# SmartShell_Schematic.net
KiCad netlist of a schematic drawn in Altium Designer
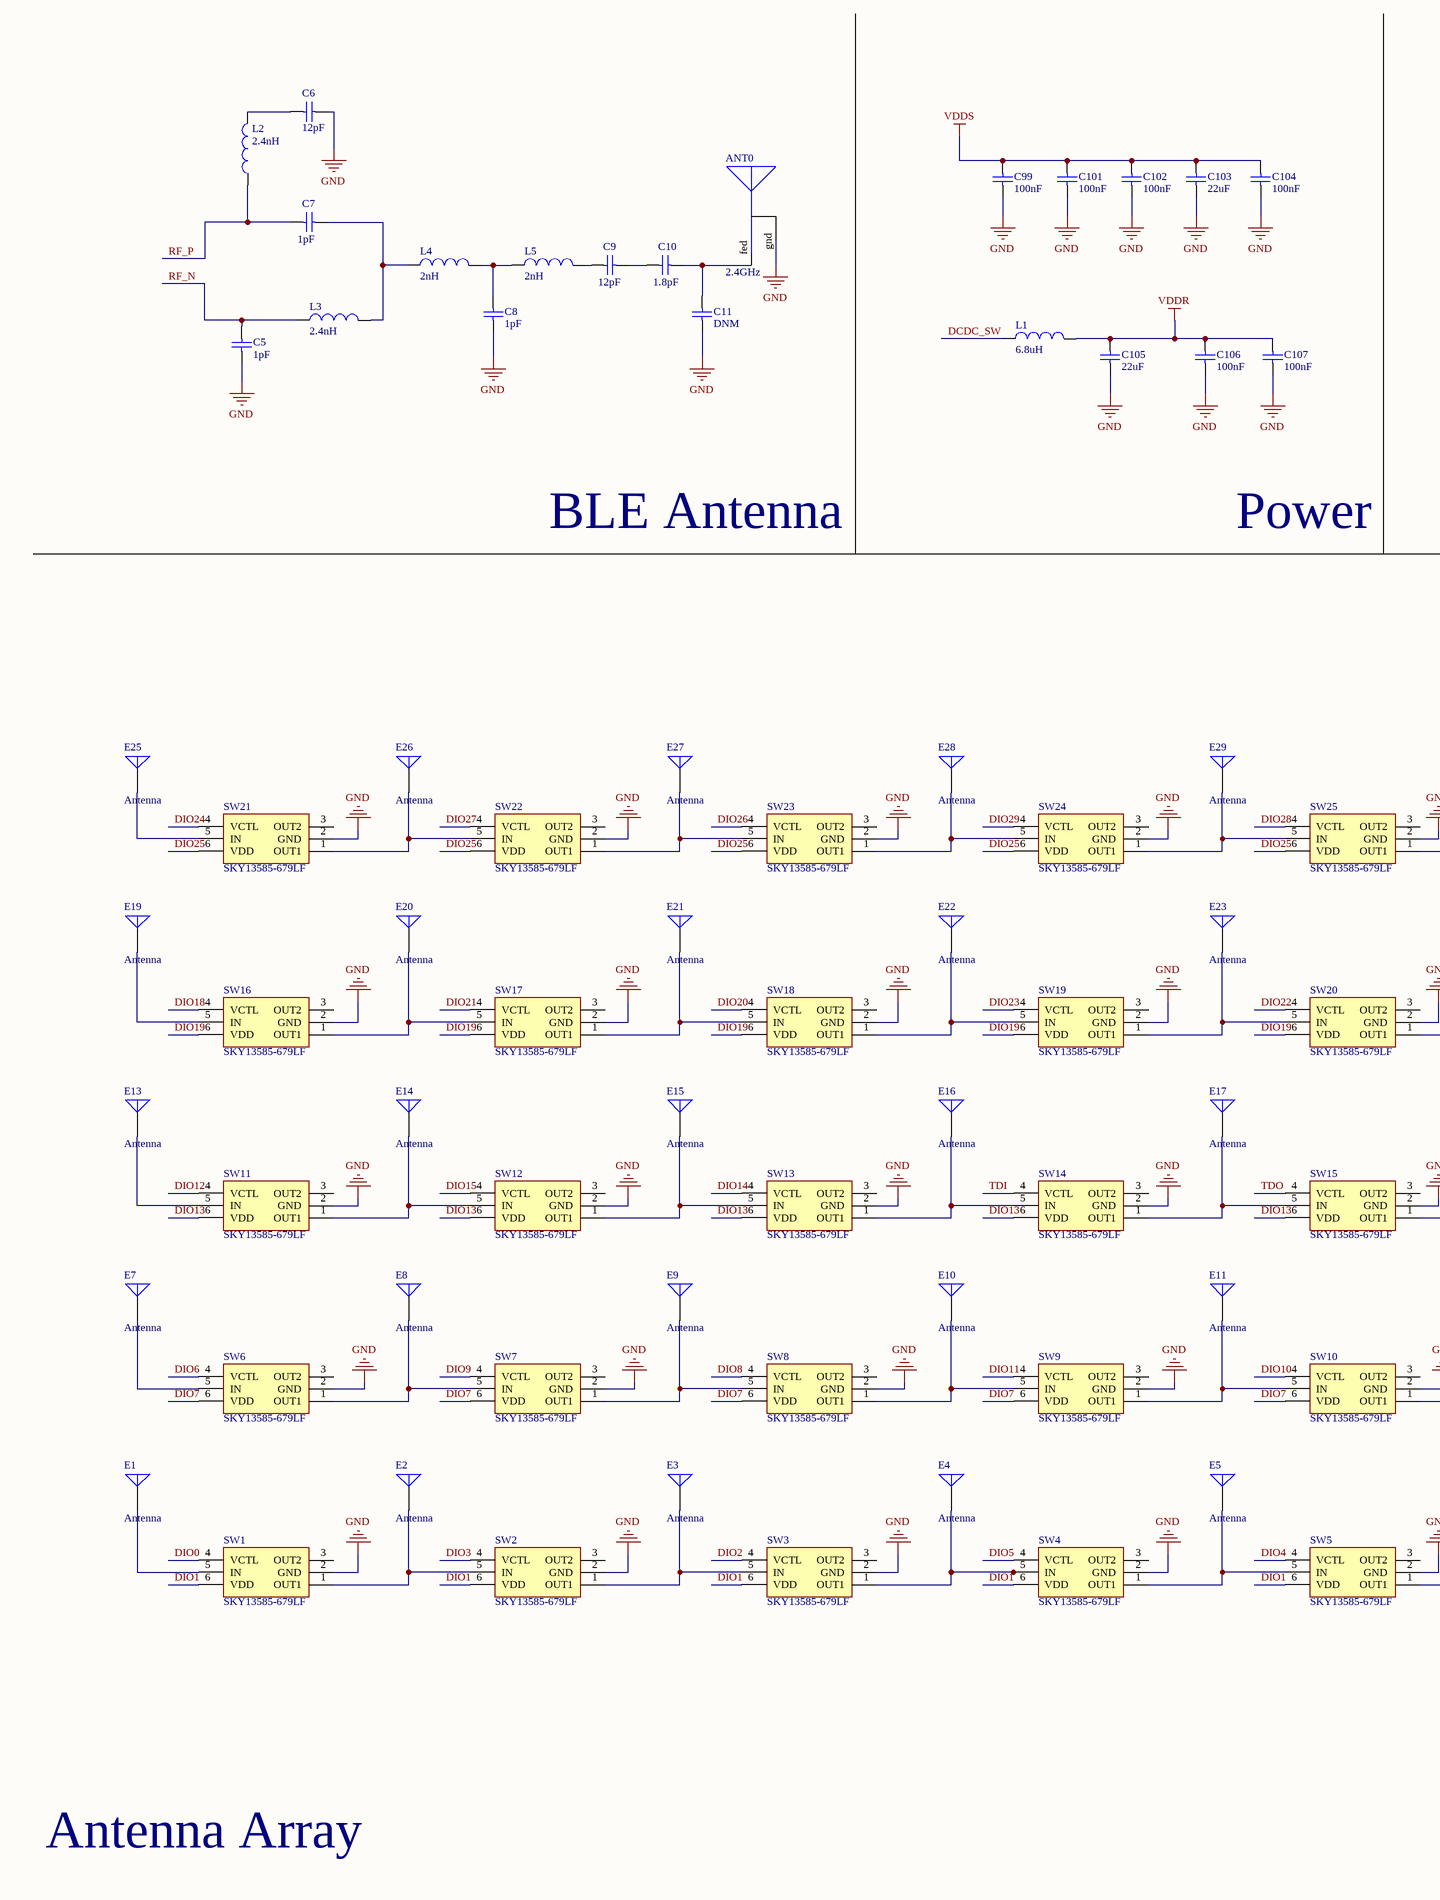
[diagram p0: SmartShell_Schematic.SchDoc, left]
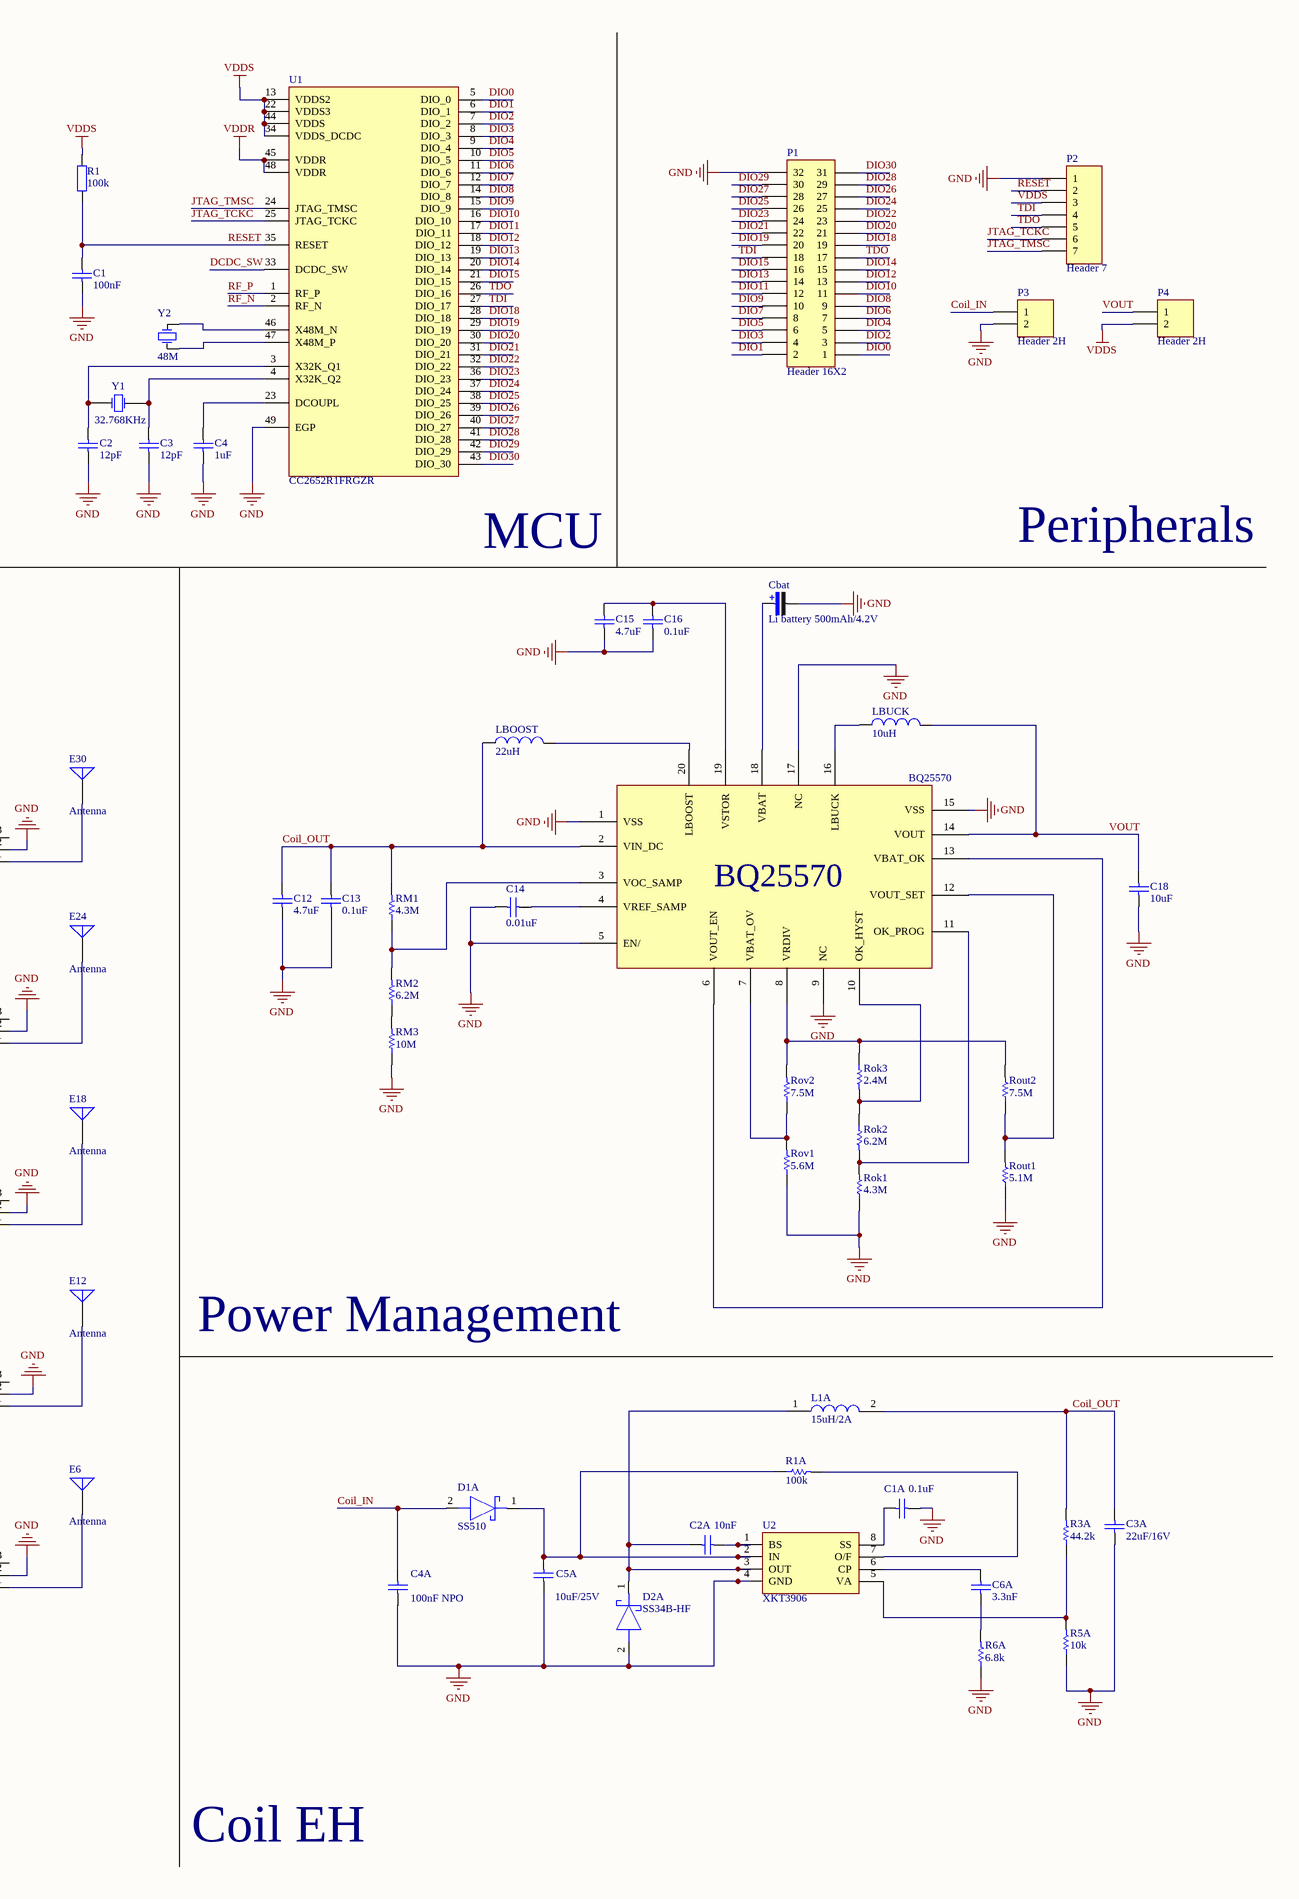
[diagram p1: SmartShell_Schematic.SchDoc, right]

(export (version "E")
  (design (tool "Eeschema 10.0.6"))
  (components
    (comp (ref "ANT0")
      (value "2.4GHz")
      (footprint "PCBComponent_1")
      (description "2.4GHz small RF-antenna")
      (libsource (lib "ant043") (part "AN043"))
    )
    (comp (ref "BQ25570") (value "~") (libsource (lib "bq25570") (part "Component_1")))
    (comp (ref "C1")
      (value "100nF")
      (footprint "C-0603")
      (description "贴片瓷片电容")
      (fields (field (name "Comment") "Cap-S") (field (name "PUBLISHER") "Altium Limited"))
      (libsource (lib "fszhang") (part "Cap-S"))
    )
    (comp (ref "C1A")
      (value "0.1uF")
      (footprint "0603")
      (description "Capacitor")
      (fields (field (name "Comment") "Cap") (field (name "PUBLISHER") "Altium Limited"))
      (libsource (lib "Miscellaneous Devices") (part "Cap"))
    )
    (comp (ref "C2")
      (value "12pF")
      (footprint "C-0603")
      (description "贴片瓷片电容")
      (fields (field (name "Comment") "Cap-S") (field (name "PUBLISHER") "Altium Limited"))
      (libsource (lib "fszhang") (part "Cap-S"))
    )
    (comp (ref "C2A")
      (value "10nF")
      (footprint "0603")
      (description "Capacitor")
      (fields (field (name "Comment") "Cap") (field (name "PUBLISHER") "Altium Limited"))
      (libsource (lib "Miscellaneous Devices") (part "Cap"))
    )
    (comp (ref "C3")
      (value "12pF")
      (footprint "C-0603")
      (description "贴片瓷片电容")
      (fields (field (name "Comment") "Cap-S") (field (name "PUBLISHER") "Altium Limited"))
      (libsource (lib "fszhang") (part "Cap-S"))
    )
    (comp (ref "C3A")
      (value "22uF/16V")
      (footprint "1206")
      (description "Capacitor")
      (fields (field (name "Comment") "Cap") (field (name "PUBLISHER") "Altium Limited"))
      (libsource (lib "Miscellaneous Devices") (part "Cap"))
    )
    (comp (ref "C4")
      (value "1uF")
      (footprint "C-0603")
      (description "贴片瓷片电容")
      (fields (field (name "Comment") "Cap-S") (field (name "PUBLISHER") "Altium Limited"))
      (libsource (lib "fszhang") (part "Cap-S"))
    )
    (comp (ref "C4A")
      (value "100nF NPO")
      (footprint "1206")
      (description "Capacitor")
      (fields (field (name "Comment") "Cap") (field (name "PUBLISHER") "Altium Limited"))
      (libsource (lib "Miscellaneous Devices") (part "Cap"))
    )
    (comp (ref "C5")
      (value "1pF")
      (footprint "RAD-0.3")
      (description "Capacitor")
      (fields (field (name "PUBLISHER") "Altium Limited"))
      (libsource (lib "Miscellaneous Devices") (part "Cap"))
    )
    (comp (ref "C5A")
      (value "10uF/25V")
      (footprint "1206")
      (description "Capacitor")
      (fields (field (name "Comment") "Cap") (field (name "PUBLISHER") "Altium Limited"))
      (libsource (lib "Miscellaneous Devices") (part "Cap"))
    )
    (comp (ref "C6")
      (value "12pF")
      (footprint "RAD-0.3")
      (description "Capacitor")
      (fields (field (name "PUBLISHER") "Altium Limited"))
      (libsource (lib "Miscellaneous Devices") (part "Cap"))
    )
    (comp (ref "C6A")
      (value "3.3nF")
      (footprint "0603")
      (description "Capacitor")
      (fields (field (name "Comment") "Cap") (field (name "PUBLISHER") "Altium Limited"))
      (libsource (lib "Miscellaneous Devices") (part "Cap"))
    )
    (comp (ref "C7")
      (value "1pF")
      (footprint "RAD-0.3")
      (description "Capacitor")
      (fields (field (name "PUBLISHER") "Altium Limited"))
      (libsource (lib "Miscellaneous Devices") (part "Cap"))
    )
    (comp (ref "C8")
      (value "1pF")
      (footprint "RAD-0.3")
      (description "Capacitor")
      (fields (field (name "PUBLISHER") "Altium Limited"))
      (libsource (lib "Miscellaneous Devices") (part "Cap"))
    )
    (comp (ref "C9")
      (value "12pF")
      (footprint "RAD-0.3")
      (description "Capacitor")
      (fields (field (name "PUBLISHER") "Altium Limited"))
      (libsource (lib "Miscellaneous Devices") (part "Cap"))
    )
    (comp (ref "C10")
      (value "1.8pF")
      (footprint "RAD-0.3")
      (description "Capacitor")
      (fields (field (name "PUBLISHER") "Altium Limited"))
      (libsource (lib "Miscellaneous Devices") (part "Cap"))
    )
    (comp (ref "C11")
      (value "DNM")
      (footprint "RAD-0.3")
      (description "Capacitor")
      (fields (field (name "PUBLISHER") "Altium Limited"))
      (libsource (lib "Miscellaneous Devices") (part "Cap"))
    )
    (comp (ref "C12")
      (value "4.7uF")
      (footprint "1608[0603]")
      (description "Capacitor")
      (fields (field (name "PUBLISHER") "Altium Limited"))
      (libsource (lib "Miscellaneous Devices") (part "Cap"))
    )
    (comp (ref "C13")
      (value "0.1uF")
      (footprint "1608[0603]")
      (description "Capacitor")
      (fields (field (name "PUBLISHER") "Altium Limited"))
      (libsource (lib "Miscellaneous Devices") (part "Cap"))
    )
    (comp (ref "C14")
      (value "0.01uF")
      (footprint "1608[0603]")
      (description "Capacitor")
      (fields (field (name "PUBLISHER") "Altium Limited"))
      (libsource (lib "Miscellaneous Devices") (part "Cap"))
    )
    (comp (ref "C15")
      (value "4.7uF")
      (footprint "1608[0603]")
      (description "Capacitor")
      (fields (field (name "PUBLISHER") "Altium Limited"))
      (libsource (lib "Miscellaneous Devices") (part "Cap"))
    )
    (comp (ref "C16")
      (value "0.1uF")
      (footprint "1608[0603]")
      (description "Capacitor")
      (fields (field (name "PUBLISHER") "Altium Limited"))
      (libsource (lib "Miscellaneous Devices") (part "Cap"))
    )
    (comp (ref "C18")
      (value "10uF")
      (footprint "1608[0603]")
      (description "Capacitor")
      (fields (field (name "PUBLISHER") "Altium Limited"))
      (libsource (lib "Miscellaneous Devices") (part "Cap"))
    )
    (comp (ref "C99")
      (value "100nF")
      (footprint "C-0603")
      (description "贴片瓷片电容")
      (fields (field (name "Comment") "Cap-S") (field (name "PUBLISHER") "Altium Limited"))
      (libsource (lib "fszhang") (part "Cap-S"))
    )
    (comp (ref "C101")
      (value "100nF")
      (footprint "C-0603")
      (description "贴片瓷片电容")
      (fields (field (name "Comment") "Cap-S") (field (name "PUBLISHER") "Altium Limited"))
      (libsource (lib "fszhang") (part "Cap-S"))
    )
    (comp (ref "C102")
      (value "100nF")
      (footprint "C-0603")
      (description "贴片瓷片电容")
      (fields (field (name "Comment") "Cap-S") (field (name "PUBLISHER") "Altium Limited"))
      (libsource (lib "fszhang") (part "Cap-S"))
    )
    (comp (ref "C103")
      (value "22uF")
      (footprint "C-0603")
      (description "贴片瓷片电容")
      (fields (field (name "Comment") "Cap-S") (field (name "PUBLISHER") "Altium Limited"))
      (libsource (lib "fszhang") (part "Cap-S"))
    )
    (comp (ref "C104")
      (value "100nF")
      (footprint "C-0603")
      (description "贴片瓷片电容")
      (fields (field (name "Comment") "Cap-S") (field (name "PUBLISHER") "Altium Limited"))
      (libsource (lib "fszhang") (part "Cap-S"))
    )
    (comp (ref "C105")
      (value "22uF")
      (footprint "C-0603")
      (description "贴片瓷片电容")
      (fields (field (name "Comment") "Cap-S") (field (name "PUBLISHER") "Altium Limited"))
      (libsource (lib "fszhang") (part "Cap-S"))
    )
    (comp (ref "C106")
      (value "100nF")
      (footprint "C-0603")
      (description "贴片瓷片电容")
      (fields (field (name "Comment") "Cap-S") (field (name "PUBLISHER") "Altium Limited"))
      (libsource (lib "fszhang") (part "Cap-S"))
    )
    (comp (ref "C107")
      (value "100nF")
      (footprint "C-0603")
      (description "贴片瓷片电容")
      (fields (field (name "Comment") "Cap-S") (field (name "PUBLISHER") "Altium Limited"))
      (libsource (lib "fszhang") (part "Cap-S"))
    )
    (comp (ref "Cbat")
      (value "Li battery 500mAh/4.2V")
      (footprint "C-RB-SD6")
      (description "贴片铝电解电容")
      (fields (field (name "Comment") "Cap-Pol-ES") (field (name "PUBLISHER") "Altium Limited"))
      (libsource (lib "fszhang") (part "Cap-Pol-ES"))
    )
    (comp (ref "D1A")
      (value "SS510")
      (footprint "SamacSys:DIOM7959X262N")
      (description "Schottky Diode")
      (libsource (lib "SamacSys") (part "SS510"))
    )
    (comp (ref "D2A")
      (value "SS34B-HF")
      (footprint "SamacSys:DIOM5336X320N")
      (description "Schottky Diode")
      (libsource (lib "SamacSys") (part "SS34B-HF"))
    )
    (comp (ref "E1")
      (value "Antenna")
      (footprint "PIN1")
      (description "Generic Antenna")
      (fields (field (name "PUBLISHER") "Altium Limited"))
      (libsource (lib "Miscellaneous Devices") (part "Antenna"))
    )
    (comp (ref "E2")
      (value "Antenna")
      (footprint "PIN1")
      (description "Generic Antenna")
      (fields (field (name "PUBLISHER") "Altium Limited"))
      (libsource (lib "Miscellaneous Devices") (part "Antenna"))
    )
    (comp (ref "E3")
      (value "Antenna")
      (footprint "PIN1")
      (description "Generic Antenna")
      (fields (field (name "PUBLISHER") "Altium Limited"))
      (libsource (lib "Miscellaneous Devices") (part "Antenna"))
    )
    (comp (ref "E4")
      (value "Antenna")
      (footprint "PIN1")
      (description "Generic Antenna")
      (fields (field (name "PUBLISHER") "Altium Limited"))
      (libsource (lib "Miscellaneous Devices") (part "Antenna"))
    )
    (comp (ref "E5")
      (value "Antenna")
      (footprint "PIN1")
      (description "Generic Antenna")
      (fields (field (name "PUBLISHER") "Altium Limited"))
      (libsource (lib "Miscellaneous Devices") (part "Antenna"))
    )
    (comp (ref "E6")
      (value "Antenna")
      (footprint "PIN1")
      (description "Generic Antenna")
      (fields (field (name "PUBLISHER") "Altium Limited"))
      (libsource (lib "Miscellaneous Devices") (part "Antenna"))
    )
    (comp (ref "E7")
      (value "Antenna")
      (footprint "PIN1")
      (description "Generic Antenna")
      (fields (field (name "PUBLISHER") "Altium Limited"))
      (libsource (lib "Miscellaneous Devices") (part "Antenna"))
    )
    (comp (ref "E8")
      (value "Antenna")
      (footprint "PIN1")
      (description "Generic Antenna")
      (fields (field (name "PUBLISHER") "Altium Limited"))
      (libsource (lib "Miscellaneous Devices") (part "Antenna"))
    )
    (comp (ref "E9")
      (value "Antenna")
      (footprint "PIN1")
      (description "Generic Antenna")
      (fields (field (name "PUBLISHER") "Altium Limited"))
      (libsource (lib "Miscellaneous Devices") (part "Antenna"))
    )
    (comp (ref "E10")
      (value "Antenna")
      (footprint "PIN1")
      (description "Generic Antenna")
      (fields (field (name "PUBLISHER") "Altium Limited"))
      (libsource (lib "Miscellaneous Devices") (part "Antenna"))
    )
    (comp (ref "E11")
      (value "Antenna")
      (footprint "PIN1")
      (description "Generic Antenna")
      (fields (field (name "PUBLISHER") "Altium Limited"))
      (libsource (lib "Miscellaneous Devices") (part "Antenna"))
    )
    (comp (ref "E12")
      (value "Antenna")
      (footprint "PIN1")
      (description "Generic Antenna")
      (fields (field (name "PUBLISHER") "Altium Limited"))
      (libsource (lib "Miscellaneous Devices") (part "Antenna"))
    )
    (comp (ref "E13")
      (value "Antenna")
      (footprint "PIN1")
      (description "Generic Antenna")
      (fields (field (name "PUBLISHER") "Altium Limited"))
      (libsource (lib "Miscellaneous Devices") (part "Antenna"))
    )
    (comp (ref "E14")
      (value "Antenna")
      (footprint "PIN1")
      (description "Generic Antenna")
      (fields (field (name "PUBLISHER") "Altium Limited"))
      (libsource (lib "Miscellaneous Devices") (part "Antenna"))
    )
    (comp (ref "E15")
      (value "Antenna")
      (footprint "PIN1")
      (description "Generic Antenna")
      (fields (field (name "PUBLISHER") "Altium Limited"))
      (libsource (lib "Miscellaneous Devices") (part "Antenna"))
    )
    (comp (ref "E16")
      (value "Antenna")
      (footprint "PIN1")
      (description "Generic Antenna")
      (fields (field (name "PUBLISHER") "Altium Limited"))
      (libsource (lib "Miscellaneous Devices") (part "Antenna"))
    )
    (comp (ref "E17")
      (value "Antenna")
      (footprint "PIN1")
      (description "Generic Antenna")
      (fields (field (name "PUBLISHER") "Altium Limited"))
      (libsource (lib "Miscellaneous Devices") (part "Antenna"))
    )
    (comp (ref "E18")
      (value "Antenna")
      (footprint "PIN1")
      (description "Generic Antenna")
      (fields (field (name "PUBLISHER") "Altium Limited"))
      (libsource (lib "Miscellaneous Devices") (part "Antenna"))
    )
    (comp (ref "E19")
      (value "Antenna")
      (footprint "PIN1")
      (description "Generic Antenna")
      (fields (field (name "PUBLISHER") "Altium Limited"))
      (libsource (lib "Miscellaneous Devices") (part "Antenna"))
    )
    (comp (ref "E20")
      (value "Antenna")
      (footprint "PIN1")
      (description "Generic Antenna")
      (fields (field (name "PUBLISHER") "Altium Limited"))
      (libsource (lib "Miscellaneous Devices") (part "Antenna"))
    )
    (comp (ref "E21")
      (value "Antenna")
      (footprint "PIN1")
      (description "Generic Antenna")
      (fields (field (name "PUBLISHER") "Altium Limited"))
      (libsource (lib "Miscellaneous Devices") (part "Antenna"))
    )
    (comp (ref "E22")
      (value "Antenna")
      (footprint "PIN1")
      (description "Generic Antenna")
      (fields (field (name "PUBLISHER") "Altium Limited"))
      (libsource (lib "Miscellaneous Devices") (part "Antenna"))
    )
    (comp (ref "E23")
      (value "Antenna")
      (footprint "PIN1")
      (description "Generic Antenna")
      (fields (field (name "PUBLISHER") "Altium Limited"))
      (libsource (lib "Miscellaneous Devices") (part "Antenna"))
    )
    (comp (ref "E24")
      (value "Antenna")
      (footprint "PIN1")
      (description "Generic Antenna")
      (fields (field (name "PUBLISHER") "Altium Limited"))
      (libsource (lib "Miscellaneous Devices") (part "Antenna"))
    )
    (comp (ref "E25")
      (value "Antenna")
      (footprint "PIN1")
      (description "Generic Antenna")
      (fields (field (name "PUBLISHER") "Altium Limited"))
      (libsource (lib "Miscellaneous Devices") (part "Antenna"))
    )
    (comp (ref "E26")
      (value "Antenna")
      (footprint "PIN1")
      (description "Generic Antenna")
      (fields (field (name "PUBLISHER") "Altium Limited"))
      (libsource (lib "Miscellaneous Devices") (part "Antenna"))
    )
    (comp (ref "E27")
      (value "Antenna")
      (footprint "PIN1")
      (description "Generic Antenna")
      (fields (field (name "PUBLISHER") "Altium Limited"))
      (libsource (lib "Miscellaneous Devices") (part "Antenna"))
    )
    (comp (ref "E28")
      (value "Antenna")
      (footprint "PIN1")
      (description "Generic Antenna")
      (fields (field (name "PUBLISHER") "Altium Limited"))
      (libsource (lib "Miscellaneous Devices") (part "Antenna"))
    )
    (comp (ref "E29")
      (value "Antenna")
      (footprint "PIN1")
      (description "Generic Antenna")
      (fields (field (name "PUBLISHER") "Altium Limited"))
      (libsource (lib "Miscellaneous Devices") (part "Antenna"))
    )
    (comp (ref "E30")
      (value "Antenna")
      (footprint "PIN1")
      (description "Generic Antenna")
      (fields (field (name "PUBLISHER") "Altium Limited"))
      (libsource (lib "Miscellaneous Devices") (part "Antenna"))
    )
    (comp (ref "L1")
      (value "6.8uH")
      (footprint "0402-A")
      (description "Inductor")
      (fields (field (name "PUBLISHER") "Altium Limited"))
      (libsource (lib "Miscellaneous Devices") (part "Inductor"))
    )
    (comp (ref "L1A")
      (value "15uH/2A")
      (footprint "SamacSys:CD73NP331KC")
      (description "Inductor")
      (fields
        (field (name "MANUFACTURER_PART_NUMBER") "CD73NP-331KC")
        (field (name "MOUSER PART NUMBER") "851-CD73NP-331KC")
      )
      (libsource (lib "SamacSys") (part "CD73NP-331KC"))
    )
    (comp (ref "L2")
      (value "2.4nH")
      (footprint "0402-A")
      (description "Inductor")
      (fields (field (name "PUBLISHER") "Altium Limited"))
      (libsource (lib "Miscellaneous Devices") (part "Inductor"))
    )
    (comp (ref "L3")
      (value "2.4nH")
      (footprint "0402-A")
      (description "Inductor")
      (fields (field (name "PUBLISHER") "Altium Limited"))
      (libsource (lib "Miscellaneous Devices") (part "Inductor"))
    )
    (comp (ref "L4")
      (value "2nH")
      (footprint "0402-A")
      (description "Inductor")
      (fields (field (name "PUBLISHER") "Altium Limited"))
      (libsource (lib "Miscellaneous Devices") (part "Inductor"))
    )
    (comp (ref "L5")
      (value "2nH")
      (footprint "0402-A")
      (description "Inductor")
      (fields (field (name "PUBLISHER") "Altium Limited"))
      (libsource (lib "Miscellaneous Devices") (part "Inductor"))
    )
    (comp (ref "LBOOST")
      (value "22uH")
      (footprint "0603")
      (description "Inductor")
      (fields (field (name "PUBLISHER") "Altium Limited"))
      (libsource (lib "Miscellaneous Devices") (part "Inductor"))
    )
    (comp (ref "LBUCK")
      (value "10uH")
      (footprint "0603")
      (description "Inductor")
      (fields (field (name "PUBLISHER") "Altium Limited"))
      (libsource (lib "Miscellaneous Devices") (part "Inductor"))
    )
    (comp (ref "P1")
      (value "Header 16X2")
      (footprint "HDR2X16")
      (description "Header, 16-Pin, Dual row")
      (fields (field (name "PUBLISHER") "Altium Limited"))
      (libsource (lib "Miscellaneous Connectors") (part "Header 16X2"))
    )
    (comp (ref "P2")
      (value "Header 7")
      (footprint "HDR1X7")
      (description "Header, 7-Pin")
      (fields (field (name "PUBLISHER") "Altium Limited"))
      (libsource (lib "Miscellaneous Connectors") (part "Header 7"))
    )
    (comp (ref "P3")
      (value "Header 2H")
      (footprint "HDR1X2H")
      (description "Header, 2-Pin, Right Angle")
      (fields (field (name "PUBLISHER") "Altium Limited"))
      (libsource (lib "Miscellaneous Connectors") (part "Header 2H"))
    )
    (comp (ref "P4")
      (value "Header 2H")
      (footprint "HDR1X2H")
      (description "Header, 2-Pin, Right Angle")
      (fields (field (name "PUBLISHER") "Altium Limited"))
      (libsource (lib "Miscellaneous Connectors") (part "Header 2H"))
    )
    (comp (ref "R1")
      (value "100k")
      (footprint "0603-1")
      (description "贴片电阻")
      (fields (field (name "Comment") "Res1") (field (name "PUBLISHER") "Altium Limited"))
      (libsource (lib "fszhang") (part "Res1"))
    )
    (comp (ref "R1A")
      (value "100k")
      (footprint "0603")
      (description "Chip Resistor (Surface Mount)")
      (fields (field (name "MANUFACTURER") "Generic Chip Res (TBD)") (field (name "Comment") "Res"))
      (libsource (lib "wisp") (part "Res"))
    )
    (comp (ref "R3A")
      (value "44.2k")
      (footprint "0603")
      (description "Chip Resistor (Surface Mount)")
      (fields (field (name "MANUFACTURER") "Generic Chip Res (TBD)") (field (name "Comment") "Res"))
      (libsource (lib "wisp") (part "Res"))
    )
    (comp (ref "R5A")
      (value "10k")
      (footprint "0603")
      (description "Chip Resistor (Surface Mount)")
      (fields (field (name "MANUFACTURER") "Generic Chip Res (TBD)") (field (name "Comment") "Res"))
      (libsource (lib "wisp") (part "Res"))
    )
    (comp (ref "R6A")
      (value "6.8k")
      (footprint "0603")
      (description "Chip Resistor (Surface Mount)")
      (fields (field (name "MANUFACTURER") "Generic Chip Res (TBD)") (field (name "Comment") "Res"))
      (libsource (lib "wisp") (part "Res"))
    )
    (comp (ref "RM1")
      (value "4.3M")
      (footprint "0402")
      (description "Resistor")
      (fields (field (name "PUBLISHER") "Altium Limited"))
      (libsource (lib "Miscellaneous Devices") (part "Res1"))
    )
    (comp (ref "RM2")
      (value "6.2M")
      (footprint "0402")
      (description "Resistor")
      (fields (field (name "PUBLISHER") "Altium Limited"))
      (libsource (lib "Miscellaneous Devices") (part "Res1"))
    )
    (comp (ref "RM3")
      (value "10M")
      (footprint "0402")
      (description "Resistor")
      (fields (field (name "PUBLISHER") "Altium Limited"))
      (libsource (lib "Miscellaneous Devices") (part "Res1"))
    )
    (comp (ref "Rok1")
      (value "4.3M")
      (footprint "0402")
      (description "Resistor")
      (fields (field (name "PUBLISHER") "Altium Limited"))
      (libsource (lib "Miscellaneous Devices") (part "Res1"))
    )
    (comp (ref "Rok2")
      (value "6.2M")
      (footprint "0402")
      (description "Resistor")
      (fields (field (name "PUBLISHER") "Altium Limited"))
      (libsource (lib "Miscellaneous Devices") (part "Res1"))
    )
    (comp (ref "Rok3")
      (value "2.4M")
      (footprint "0402")
      (description "Resistor")
      (fields (field (name "PUBLISHER") "Altium Limited"))
      (libsource (lib "Miscellaneous Devices") (part "Res1"))
    )
    (comp (ref "Rout1")
      (value "5.1M")
      (footprint "0402")
      (description "Resistor")
      (fields (field (name "PUBLISHER") "Altium Limited"))
      (libsource (lib "Miscellaneous Devices") (part "Res1"))
    )
    (comp (ref "Rout2")
      (value "7.5M")
      (footprint "0402")
      (description "Resistor")
      (fields (field (name "PUBLISHER") "Altium Limited"))
      (libsource (lib "Miscellaneous Devices") (part "Res1"))
    )
    (comp (ref "Rov1")
      (value "5.6M")
      (footprint "0402")
      (description "Resistor")
      (fields (field (name "PUBLISHER") "Altium Limited"))
      (libsource (lib "Miscellaneous Devices") (part "Res1"))
    )
    (comp (ref "Rov2")
      (value "7.5M")
      (footprint "0402")
      (description "Resistor")
      (fields (field (name "PUBLISHER") "Altium Limited"))
      (libsource (lib "Miscellaneous Devices") (part "Res1"))
    )
    (comp (ref "SW1") (value "SKY13585-679LF") (libsource (lib "SKY13585_679LF") (part "Component_1")))
    (comp (ref "SW2") (value "SKY13585-679LF") (libsource (lib "SKY13585_679LF") (part "Component_1")))
    (comp (ref "SW3") (value "SKY13585-679LF") (libsource (lib "SKY13585_679LF") (part "Component_1")))
    (comp (ref "SW4") (value "SKY13585-679LF") (libsource (lib "SKY13585_679LF") (part "Component_1")))
    (comp (ref "SW5") (value "SKY13585-679LF") (libsource (lib "SKY13585_679LF") (part "Component_1")))
    (comp (ref "SW6") (value "SKY13585-679LF") (libsource (lib "SKY13585_679LF") (part "Component_1")))
    (comp (ref "SW7") (value "SKY13585-679LF") (libsource (lib "SKY13585_679LF") (part "Component_1")))
    (comp (ref "SW8") (value "SKY13585-679LF") (libsource (lib "SKY13585_679LF") (part "Component_1")))
    (comp (ref "SW9") (value "SKY13585-679LF") (libsource (lib "SKY13585_679LF") (part "Component_1")))
    (comp (ref "SW10") (value "SKY13585-679LF") (libsource (lib "SKY13585_679LF") (part "Component_1")))
    (comp (ref "SW11") (value "SKY13585-679LF") (libsource (lib "SKY13585_679LF") (part "Component_1")))
    (comp (ref "SW12") (value "SKY13585-679LF") (libsource (lib "SKY13585_679LF") (part "Component_1")))
    (comp (ref "SW13") (value "SKY13585-679LF") (libsource (lib "SKY13585_679LF") (part "Component_1")))
    (comp (ref "SW14") (value "SKY13585-679LF") (libsource (lib "SKY13585_679LF") (part "Component_1")))
    (comp (ref "SW15") (value "SKY13585-679LF") (libsource (lib "SKY13585_679LF") (part "Component_1")))
    (comp (ref "SW16") (value "SKY13585-679LF") (libsource (lib "SKY13585_679LF") (part "Component_1")))
    (comp (ref "SW17") (value "SKY13585-679LF") (libsource (lib "SKY13585_679LF") (part "Component_1")))
    (comp (ref "SW18") (value "SKY13585-679LF") (libsource (lib "SKY13585_679LF") (part "Component_1")))
    (comp (ref "SW19") (value "SKY13585-679LF") (libsource (lib "SKY13585_679LF") (part "Component_1")))
    (comp (ref "SW20") (value "SKY13585-679LF") (libsource (lib "SKY13585_679LF") (part "Component_1")))
    (comp (ref "SW21") (value "SKY13585-679LF") (libsource (lib "SKY13585_679LF") (part "Component_1")))
    (comp (ref "SW22") (value "SKY13585-679LF") (libsource (lib "SKY13585_679LF") (part "Component_1")))
    (comp (ref "SW23") (value "SKY13585-679LF") (libsource (lib "SKY13585_679LF") (part "Component_1")))
    (comp (ref "SW24") (value "SKY13585-679LF") (libsource (lib "SKY13585_679LF") (part "Component_1")))
    (comp (ref "SW25") (value "SKY13585-679LF") (libsource (lib "SKY13585_679LF") (part "Component_1")))
    (comp (ref "U1") (value "CC2652R1FRGZR") (libsource (lib "CC2652R1FRGZ") (part "Component_1")))
    (comp (ref "U2") (value "XKT3906") (libsource (lib "XKT-3906") (part "Component_1")))
    (comp (ref "Y1")
      (value "32.768KHz")
      (footprint "R38")
      (description "Crystal Oscillator")
      (fields (field (name "PUBLISHER") "Altium Limited"))
      (libsource (lib "Miscellaneous Devices") (part "XTAL"))
    )
    (comp (ref "Y2")
      (value "48M")
      (footprint "X-HC-49S")
      (description "晶振")
      (fields (field (name "Comment") "XTAL") (field (name "PUBLISHER") "Altium Limited"))
      (libsource (lib "fszhang") (part "XTAL"))
    )
  )
  (nets
    (net (code "1") (name "/Coil_IN") (class "Default")
      (node (ref "C4A") (pin "2") (pinfunction "2_2") (pintype "passive"))
      (node (ref "D1A") (pin "2") (pinfunction "A_2") (pintype "passive"))
      (node (ref "P3") (pin "1") (pinfunction "1_1") (pintype "passive"))
    )
    (net (code "2") (name "/Coil_OUT") (class "Default")
      (node (ref "BQ25570") (pin "2") (pinfunction "VIN_DC_2") (pintype "passive"))
      (node (ref "C12") (pin "2") (pinfunction "2_2") (pintype "passive"))
      (node (ref "C13") (pin "2") (pinfunction "2_2") (pintype "passive"))
      (node (ref "C3A") (pin "1") (pinfunction "1_1") (pintype "passive"))
      (node (ref "L1A") (pin "2") (pinfunction "2_2") (pintype "passive"))
      (node (ref "LBOOST") (pin "1") (pinfunction "1_1") (pintype "passive"))
      (node (ref "R3A") (pin "2") (pinfunction "2_2") (pintype "passive"))
      (node (ref "RM1") (pin "2") (pinfunction "2_2") (pintype "passive"))
    )
    (net (code "3") (name "/DCDC_SW") (class "Default")
      (node (ref "L1") (pin "1") (pinfunction "1_1") (pintype "passive"))
      (node (ref "U1") (pin "33") (pinfunction "DCDC_SW_33") (pintype "passive"))
    )
    (net (code "4") (name "/DIO0") (class "Default")
      (node (ref "P1") (pin "1") (pinfunction "1_1") (pintype "passive"))
      (node (ref "SW1") (pin "4") (pinfunction "VCTL_4") (pintype "passive"))
      (node (ref "U1") (pin "5") (pinfunction "DIO_0_5") (pintype "passive"))
    )
    (net (code "5") (name "/DIO1") (class "Default")
      (node (ref "P1") (pin "2") (pinfunction "2_2") (pintype "passive"))
      (node (ref "SW1") (pin "6") (pinfunction "VDD_6") (pintype "passive"))
      (node (ref "SW2") (pin "6") (pinfunction "VDD_6") (pintype "passive"))
      (node (ref "SW3") (pin "6") (pinfunction "VDD_6") (pintype "passive"))
      (node (ref "SW4") (pin "6") (pinfunction "VDD_6") (pintype "passive"))
      (node (ref "SW5") (pin "6") (pinfunction "VDD_6") (pintype "passive"))
      (node (ref "U1") (pin "6") (pinfunction "DIO_1_6") (pintype "passive"))
    )
    (net (code "6") (name "/DIO2") (class "Default")
      (node (ref "P1") (pin "3") (pinfunction "3_3") (pintype "passive"))
      (node (ref "SW3") (pin "4") (pinfunction "VCTL_4") (pintype "passive"))
      (node (ref "U1") (pin "7") (pinfunction "DIO_2_7") (pintype "passive"))
    )
    (net (code "7") (name "/DIO3") (class "Default")
      (node (ref "P1") (pin "4") (pinfunction "4_4") (pintype "passive"))
      (node (ref "SW2") (pin "4") (pinfunction "VCTL_4") (pintype "passive"))
      (node (ref "U1") (pin "8") (pinfunction "DIO_3_8") (pintype "passive"))
    )
    (net (code "8") (name "/DIO4") (class "Default")
      (node (ref "P1") (pin "5") (pinfunction "5_5") (pintype "passive"))
      (node (ref "SW5") (pin "4") (pinfunction "VCTL_4") (pintype "passive"))
      (node (ref "U1") (pin "9") (pinfunction "DIO_4_9") (pintype "passive"))
    )
    (net (code "9") (name "/DIO5") (class "Default")
      (node (ref "P1") (pin "6") (pinfunction "6_6") (pintype "passive"))
      (node (ref "SW4") (pin "4") (pinfunction "VCTL_4") (pintype "passive"))
      (node (ref "U1") (pin "10") (pinfunction "DIO_5_10") (pintype "passive"))
    )
    (net (code "10") (name "/DIO6") (class "Default")
      (node (ref "P1") (pin "7") (pinfunction "7_7") (pintype "passive"))
      (node (ref "SW6") (pin "4") (pinfunction "VCTL_4") (pintype "passive"))
      (node (ref "U1") (pin "11") (pinfunction "DIO_6_11") (pintype "passive"))
    )
    (net (code "11") (name "/DIO7") (class "Default")
      (node (ref "P1") (pin "8") (pinfunction "8_8") (pintype "passive"))
      (node (ref "SW10") (pin "6") (pinfunction "VDD_6") (pintype "passive"))
      (node (ref "SW6") (pin "6") (pinfunction "VDD_6") (pintype "passive"))
      (node (ref "SW7") (pin "6") (pinfunction "VDD_6") (pintype "passive"))
      (node (ref "SW8") (pin "6") (pinfunction "VDD_6") (pintype "passive"))
      (node (ref "SW9") (pin "6") (pinfunction "VDD_6") (pintype "passive"))
      (node (ref "U1") (pin "12") (pinfunction "DIO_7_12") (pintype "passive"))
    )
    (net (code "12") (name "/DIO8") (class "Default")
      (node (ref "P1") (pin "9") (pinfunction "9_9") (pintype "passive"))
      (node (ref "SW8") (pin "4") (pinfunction "VCTL_4") (pintype "passive"))
      (node (ref "U1") (pin "14") (pinfunction "DIO_8_14") (pintype "passive"))
    )
    (net (code "13") (name "/DIO9") (class "Default")
      (node (ref "P1") (pin "10") (pinfunction "10_10") (pintype "passive"))
      (node (ref "SW7") (pin "4") (pinfunction "VCTL_4") (pintype "passive"))
      (node (ref "U1") (pin "15") (pinfunction "DIO_9_15") (pintype "passive"))
    )
    (net (code "14") (name "/DIO10") (class "Default")
      (node (ref "P1") (pin "11") (pinfunction "11_11") (pintype "passive"))
      (node (ref "SW10") (pin "4") (pinfunction "VCTL_4") (pintype "passive"))
      (node (ref "U1") (pin "16") (pinfunction "DIO_10_16") (pintype "passive"))
    )
    (net (code "15") (name "/DIO11") (class "Default")
      (node (ref "P1") (pin "12") (pinfunction "12_12") (pintype "passive"))
      (node (ref "SW9") (pin "4") (pinfunction "VCTL_4") (pintype "passive"))
      (node (ref "U1") (pin "17") (pinfunction "DIO_11_17") (pintype "passive"))
    )
    (net (code "16") (name "/DIO12") (class "Default")
      (node (ref "P1") (pin "13") (pinfunction "13_13") (pintype "passive"))
      (node (ref "SW11") (pin "4") (pinfunction "VCTL_4") (pintype "passive"))
      (node (ref "U1") (pin "18") (pinfunction "DIO_12_18") (pintype "passive"))
    )
    (net (code "17") (name "/DIO13") (class "Default")
      (node (ref "P1") (pin "14") (pinfunction "14_14") (pintype "passive"))
      (node (ref "SW11") (pin "6") (pinfunction "VDD_6") (pintype "passive"))
      (node (ref "SW12") (pin "6") (pinfunction "VDD_6") (pintype "passive"))
      (node (ref "SW13") (pin "6") (pinfunction "VDD_6") (pintype "passive"))
      (node (ref "SW14") (pin "6") (pinfunction "VDD_6") (pintype "passive"))
      (node (ref "SW15") (pin "6") (pinfunction "VDD_6") (pintype "passive"))
      (node (ref "U1") (pin "19") (pinfunction "DIO_13_19") (pintype "passive"))
    )
    (net (code "18") (name "/DIO14") (class "Default")
      (node (ref "P1") (pin "15") (pinfunction "15_15") (pintype "passive"))
      (node (ref "SW13") (pin "4") (pinfunction "VCTL_4") (pintype "passive"))
      (node (ref "U1") (pin "20") (pinfunction "DIO_14_20") (pintype "passive"))
    )
    (net (code "19") (name "/DIO15") (class "Default")
      (node (ref "P1") (pin "16") (pinfunction "16_16") (pintype "passive"))
      (node (ref "SW12") (pin "4") (pinfunction "VCTL_4") (pintype "passive"))
      (node (ref "U1") (pin "21") (pinfunction "DIO_15_21") (pintype "passive"))
    )
    (net (code "20") (name "/DIO18") (class "Default")
      (node (ref "P1") (pin "19") (pinfunction "19_19") (pintype "passive"))
      (node (ref "SW16") (pin "4") (pinfunction "VCTL_4") (pintype "passive"))
      (node (ref "U1") (pin "28") (pinfunction "DIO_18_28") (pintype "passive"))
    )
    (net (code "21") (name "/DIO19") (class "Default")
      (node (ref "P1") (pin "20") (pinfunction "20_20") (pintype "passive"))
      (node (ref "SW16") (pin "6") (pinfunction "VDD_6") (pintype "passive"))
      (node (ref "SW17") (pin "6") (pinfunction "VDD_6") (pintype "passive"))
      (node (ref "SW18") (pin "6") (pinfunction "VDD_6") (pintype "passive"))
      (node (ref "SW19") (pin "6") (pinfunction "VDD_6") (pintype "passive"))
      (node (ref "SW20") (pin "6") (pinfunction "VDD_6") (pintype "passive"))
      (node (ref "U1") (pin "29") (pinfunction "DIO_19_29") (pintype "passive"))
    )
    (net (code "22") (name "/DIO20") (class "Default")
      (node (ref "P1") (pin "21") (pinfunction "21_21") (pintype "passive"))
      (node (ref "SW18") (pin "4") (pinfunction "VCTL_4") (pintype "passive"))
      (node (ref "U1") (pin "30") (pinfunction "DIO_20_30") (pintype "passive"))
    )
    (net (code "23") (name "/DIO21") (class "Default")
      (node (ref "P1") (pin "22") (pinfunction "22_22") (pintype "passive"))
      (node (ref "SW17") (pin "4") (pinfunction "VCTL_4") (pintype "passive"))
      (node (ref "U1") (pin "31") (pinfunction "DIO_21_31") (pintype "passive"))
    )
    (net (code "24") (name "/DIO22") (class "Default")
      (node (ref "P1") (pin "23") (pinfunction "23_23") (pintype "passive"))
      (node (ref "SW20") (pin "4") (pinfunction "VCTL_4") (pintype "passive"))
      (node (ref "U1") (pin "32") (pinfunction "DIO_22_32") (pintype "passive"))
    )
    (net (code "25") (name "/DIO23") (class "Default")
      (node (ref "P1") (pin "24") (pinfunction "24_24") (pintype "passive"))
      (node (ref "SW19") (pin "4") (pinfunction "VCTL_4") (pintype "passive"))
      (node (ref "U1") (pin "36") (pinfunction "DIO_23_36") (pintype "passive"))
    )
    (net (code "26") (name "/DIO24") (class "Default")
      (node (ref "P1") (pin "25") (pinfunction "25_25") (pintype "passive"))
      (node (ref "SW21") (pin "4") (pinfunction "VCTL_4") (pintype "passive"))
      (node (ref "U1") (pin "37") (pinfunction "DIO_24_37") (pintype "passive"))
    )
    (net (code "27") (name "/DIO25") (class "Default")
      (node (ref "P1") (pin "26") (pinfunction "26_26") (pintype "passive"))
      (node (ref "SW21") (pin "6") (pinfunction "VDD_6") (pintype "passive"))
      (node (ref "SW22") (pin "6") (pinfunction "VDD_6") (pintype "passive"))
      (node (ref "SW23") (pin "6") (pinfunction "VDD_6") (pintype "passive"))
      (node (ref "SW24") (pin "6") (pinfunction "VDD_6") (pintype "passive"))
      (node (ref "SW25") (pin "6") (pinfunction "VDD_6") (pintype "passive"))
      (node (ref "U1") (pin "38") (pinfunction "DIO_25_38") (pintype "passive"))
    )
    (net (code "28") (name "/DIO26") (class "Default")
      (node (ref "P1") (pin "27") (pinfunction "27_27") (pintype "passive"))
      (node (ref "SW23") (pin "4") (pinfunction "VCTL_4") (pintype "passive"))
      (node (ref "U1") (pin "39") (pinfunction "DIO_26_39") (pintype "passive"))
    )
    (net (code "29") (name "/DIO27") (class "Default")
      (node (ref "P1") (pin "28") (pinfunction "28_28") (pintype "passive"))
      (node (ref "SW22") (pin "4") (pinfunction "VCTL_4") (pintype "passive"))
      (node (ref "U1") (pin "40") (pinfunction "DIO_27_40") (pintype "passive"))
    )
    (net (code "30") (name "/DIO28") (class "Default")
      (node (ref "P1") (pin "29") (pinfunction "29_29") (pintype "passive"))
      (node (ref "SW25") (pin "4") (pinfunction "VCTL_4") (pintype "passive"))
      (node (ref "U1") (pin "41") (pinfunction "DIO_28_41") (pintype "passive"))
    )
    (net (code "31") (name "/DIO29") (class "Default")
      (node (ref "P1") (pin "30") (pinfunction "30_30") (pintype "passive"))
      (node (ref "SW24") (pin "4") (pinfunction "VCTL_4") (pintype "passive"))
      (node (ref "U1") (pin "42") (pinfunction "DIO_29_42") (pintype "passive"))
    )
    (net (code "32") (name "/DIO30") (class "Default")
      (node (ref "P1") (pin "31") (pinfunction "31_31") (pintype "passive"))
      (node (ref "U1") (pin "43") (pinfunction "DIO_30_43") (pintype "passive"))
    )
    (net (code "33") (name "/JTAG_TCKC") (class "Default")
      (node (ref "P2") (pin "6") (pinfunction "6_6") (pintype "passive"))
      (node (ref "U1") (pin "25") (pinfunction "JTAG_TCKC_25") (pintype "passive"))
    )
    (net (code "34") (name "/JTAG_TMSC") (class "Default")
      (node (ref "P2") (pin "7") (pinfunction "7_7") (pintype "passive"))
      (node (ref "U1") (pin "24") (pinfunction "JTAG_TMSC_24") (pintype "passive"))
    )
    (net (code "35") (name "/RESET") (class "Default")
      (node (ref "C1") (pin "2") (pinfunction "2_2") (pintype "passive"))
      (node (ref "P2") (pin "2") (pinfunction "2_2") (pintype "passive"))
      (node (ref "R1") (pin "1") (pinfunction "1_1") (pintype "passive"))
      (node (ref "U1") (pin "35") (pinfunction "RESET_35") (pintype "passive"))
    )
    (net (code "36") (name "/RF_N") (class "Default")
      (node (ref "C5") (pin "1") (pinfunction "1_1") (pintype "passive"))
      (node (ref "L3") (pin "1") (pinfunction "1_1") (pintype "passive"))
      (node (ref "U1") (pin "2") (pinfunction "RF_N_2") (pintype "passive"))
    )
    (net (code "37") (name "/RF_P") (class "Default")
      (node (ref "C7") (pin "1") (pinfunction "1_1") (pintype "passive"))
      (node (ref "L2") (pin "1") (pinfunction "1_1") (pintype "passive"))
      (node (ref "U1") (pin "1") (pinfunction "RF_P_1") (pintype "passive"))
    )
    (net (code "38") (name "/TDI") (class "Default")
      (node (ref "P1") (pin "18") (pinfunction "18_18") (pintype "passive"))
      (node (ref "P2") (pin "4") (pinfunction "4_4") (pintype "passive"))
      (node (ref "SW14") (pin "4") (pinfunction "VCTL_4") (pintype "passive"))
      (node (ref "U1") (pin "27") (pinfunction "DIO_17_27") (pintype "passive"))
    )
    (net (code "39") (name "/TDO") (class "Default")
      (node (ref "P1") (pin "17") (pinfunction "17_17") (pintype "passive"))
      (node (ref "P2") (pin "5") (pinfunction "5_5") (pintype "passive"))
      (node (ref "SW15") (pin "4") (pinfunction "VCTL_4") (pintype "passive"))
      (node (ref "U1") (pin "26") (pinfunction "DIO_16_26") (pintype "passive"))
    )
    (net (code "40") (name "/VOUT") (class "Default")
      (node (ref "BQ25570") (pin "14") (pinfunction "VOUT_14") (pintype "passive"))
      (node (ref "C18") (pin "2") (pinfunction "2_2") (pintype "passive"))
      (node (ref "LBUCK") (pin "2") (pinfunction "2_2") (pintype "passive"))
      (node (ref "P4") (pin "1") (pinfunction "1_1") (pintype "passive"))
    )
    (net (code "41") (name "GND") (class "Default")
      (node (ref "ANT0") (pin "gnd") (pinfunction "gnd_gnd") (pintype "passive"))
      (node (ref "BQ25570") (pin "1") (pinfunction "VSS_1") (pintype "passive"))
      (node (ref "BQ25570") (pin "15") (pinfunction "VSS_15") (pintype "passive"))
      (node (ref "BQ25570") (pin "17") (pinfunction "NC_17") (pintype "passive"))
      (node (ref "BQ25570") (pin "5") (pinfunction "EN/_5") (pintype "passive"))
      (node (ref "BQ25570") (pin "9") (pinfunction "NC_9") (pintype "passive"))
      (node (ref "C1") (pin "1") (pinfunction "1_1") (pintype "passive"))
      (node (ref "C101") (pin "1") (pinfunction "1_1") (pintype "passive"))
      (node (ref "C102") (pin "1") (pinfunction "1_1") (pintype "passive"))
      (node (ref "C103") (pin "1") (pinfunction "1_1") (pintype "passive"))
      (node (ref "C104") (pin "1") (pinfunction "1_1") (pintype "passive"))
      (node (ref "C105") (pin "1") (pinfunction "1_1") (pintype "passive"))
      (node (ref "C106") (pin "1") (pinfunction "1_1") (pintype "passive"))
      (node (ref "C107") (pin "1") (pinfunction "1_1") (pintype "passive"))
      (node (ref "C11") (pin "1") (pinfunction "1_1") (pintype "passive"))
      (node (ref "C12") (pin "1") (pinfunction "1_1") (pintype "passive"))
      (node (ref "C13") (pin "1") (pinfunction "1_1") (pintype "passive"))
      (node (ref "C14") (pin "2") (pinfunction "2_2") (pintype "passive"))
      (node (ref "C15") (pin "2") (pinfunction "2_2") (pintype "passive"))
      (node (ref "C16") (pin "1") (pinfunction "1_1") (pintype "passive"))
      (node (ref "C18") (pin "1") (pinfunction "1_1") (pintype "passive"))
      (node (ref "C1A") (pin "1") (pinfunction "1_1") (pintype "passive"))
      (node (ref "C2") (pin "1") (pinfunction "1_1") (pintype "passive"))
      (node (ref "C3") (pin "1") (pinfunction "1_1") (pintype "passive"))
      (node (ref "C3A") (pin "2") (pinfunction "2_2") (pintype "passive"))
      (node (ref "C4") (pin "1") (pinfunction "1_1") (pintype "passive"))
      (node (ref "C4A") (pin "1") (pinfunction "1_1") (pintype "passive"))
      (node (ref "C5") (pin "2") (pinfunction "2_2") (pintype "passive"))
      (node (ref "C5A") (pin "1") (pinfunction "1_1") (pintype "passive"))
      (node (ref "C6") (pin "2") (pinfunction "2_2") (pintype "passive"))
      (node (ref "C8") (pin "1") (pinfunction "1_1") (pintype "passive"))
      (node (ref "C99") (pin "1") (pinfunction "1_1") (pintype "passive"))
      (node (ref "Cbat") (pin "2") (pinfunction "2_2") (pintype "passive"))
      (node (ref "D2A") (pin "2") (pinfunction "A_2") (pintype "passive"))
      (node (ref "P1") (pin "32") (pinfunction "32_32") (pintype "passive"))
      (node (ref "P2") (pin "1") (pinfunction "1_1") (pintype "passive"))
      (node (ref "P3") (pin "2") (pinfunction "2_2") (pintype "passive"))
      (node (ref "R5A") (pin "1") (pinfunction "1_1") (pintype "passive"))
      (node (ref "R6A") (pin "1") (pinfunction "1_1") (pintype "passive"))
      (node (ref "RM3") (pin "1") (pinfunction "1_1") (pintype "passive"))
      (node (ref "Rok1") (pin "1") (pinfunction "1_1") (pintype "passive"))
      (node (ref "Rout1") (pin "1") (pinfunction "1_1") (pintype "passive"))
      (node (ref "Rov1") (pin "1") (pinfunction "1_1") (pintype "passive"))
      (node (ref "SW1") (pin "2") (pinfunction "GND_2") (pintype "passive"))
      (node (ref "SW10") (pin "2") (pinfunction "GND_2") (pintype "passive"))
      (node (ref "SW11") (pin "2") (pinfunction "GND_2") (pintype "passive"))
      (node (ref "SW12") (pin "2") (pinfunction "GND_2") (pintype "passive"))
      (node (ref "SW13") (pin "2") (pinfunction "GND_2") (pintype "passive"))
      (node (ref "SW14") (pin "2") (pinfunction "GND_2") (pintype "passive"))
      (node (ref "SW15") (pin "2") (pinfunction "GND_2") (pintype "passive"))
      (node (ref "SW16") (pin "2") (pinfunction "GND_2") (pintype "passive"))
      (node (ref "SW17") (pin "2") (pinfunction "GND_2") (pintype "passive"))
      (node (ref "SW18") (pin "2") (pinfunction "GND_2") (pintype "passive"))
      (node (ref "SW19") (pin "2") (pinfunction "GND_2") (pintype "passive"))
      (node (ref "SW2") (pin "2") (pinfunction "GND_2") (pintype "passive"))
      (node (ref "SW20") (pin "2") (pinfunction "GND_2") (pintype "passive"))
      (node (ref "SW21") (pin "2") (pinfunction "GND_2") (pintype "passive"))
      (node (ref "SW22") (pin "2") (pinfunction "GND_2") (pintype "passive"))
      (node (ref "SW23") (pin "2") (pinfunction "GND_2") (pintype "passive"))
      (node (ref "SW24") (pin "2") (pinfunction "GND_2") (pintype "passive"))
      (node (ref "SW25") (pin "2") (pinfunction "GND_2") (pintype "passive"))
      (node (ref "SW3") (pin "2") (pinfunction "GND_2") (pintype "passive"))
      (node (ref "SW4") (pin "2") (pinfunction "GND_2") (pintype "passive"))
      (node (ref "SW5") (pin "2") (pinfunction "GND_2") (pintype "passive"))
      (node (ref "SW6") (pin "2") (pinfunction "GND_2") (pintype "passive"))
      (node (ref "SW7") (pin "2") (pinfunction "GND_2") (pintype "passive"))
      (node (ref "SW8") (pin "2") (pinfunction "GND_2") (pintype "passive"))
      (node (ref "SW9") (pin "2") (pinfunction "GND_2") (pintype "passive"))
      (node (ref "U1") (pin "49") (pinfunction "EGP_49") (pintype "passive"))
      (node (ref "U2") (pin "4") (pinfunction "GND_4") (pintype "passive"))
    )
    (net (code "42") (name "Net-(ANT0-9)") (class "Default")
      (node (ref "ANT0") (pin "fed") (pinfunction "9_fed") (pintype "passive"))
      (node (ref "C10") (pin "2") (pinfunction "2_2") (pintype "passive"))
      (node (ref "C11") (pin "2") (pinfunction "2_2") (pintype "passive"))
    )
    (net (code "43") (name "Net-(BQ25570-LBOOST)") (class "Default")
      (node (ref "BQ25570") (pin "20") (pinfunction "LBOOST_20") (pintype "passive"))
      (node (ref "LBOOST") (pin "2") (pinfunction "2_2") (pintype "passive"))
    )
    (net (code "44") (name "Net-(BQ25570-LBUCK)") (class "Default")
      (node (ref "BQ25570") (pin "16") (pinfunction "LBUCK_16") (pintype "passive"))
      (node (ref "LBUCK") (pin "1") (pinfunction "1_1") (pintype "passive"))
    )
    (net (code "45") (name "Net-(BQ25570-OK_HYST)") (class "Default")
      (node (ref "BQ25570") (pin "10") (pinfunction "OK_HYST_10") (pintype "passive"))
      (node (ref "Rok2") (pin "1") (pinfunction "1_1") (pintype "passive"))
      (node (ref "Rok3") (pin "2") (pinfunction "2_2") (pintype "passive"))
    )
    (net (code "46") (name "Net-(BQ25570-OK_PROG)") (class "Default")
      (node (ref "BQ25570") (pin "11") (pinfunction "OK_PROG_11") (pintype "passive"))
      (node (ref "Rok1") (pin "2") (pinfunction "2_2") (pintype "passive"))
      (node (ref "Rok2") (pin "2") (pinfunction "2_2") (pintype "passive"))
    )
    (net (code "47") (name "Net-(BQ25570-VBAT)") (class "Default")
      (node (ref "BQ25570") (pin "18") (pinfunction "VBAT_18") (pintype "passive"))
      (node (ref "Cbat") (pin "1") (pinfunction "1_1") (pintype "passive"))
    )
    (net (code "48") (name "Net-(BQ25570-VBAT_OK)") (class "Default")
      (node (ref "BQ25570") (pin "13") (pinfunction "VBAT_OK_13") (pintype "passive"))
      (node (ref "BQ25570") (pin "6") (pinfunction "VOUT_EN_6") (pintype "passive"))
    )
    (net (code "49") (name "Net-(BQ25570-VBAT_OV)") (class "Default")
      (node (ref "BQ25570") (pin "7") (pinfunction "VBAT_OV_7") (pintype "passive"))
      (node (ref "Rov1") (pin "2") (pinfunction "2_2") (pintype "passive"))
      (node (ref "Rov2") (pin "1") (pinfunction "1_1") (pintype "passive"))
    )
    (net (code "50") (name "Net-(BQ25570-VOC_SAMP)") (class "Default")
      (node (ref "BQ25570") (pin "3") (pinfunction "VOC_SAMP_3") (pintype "passive"))
      (node (ref "RM1") (pin "1") (pinfunction "1_1") (pintype "passive"))
      (node (ref "RM2") (pin "2") (pinfunction "2_2") (pintype "passive"))
    )
    (net (code "51") (name "Net-(BQ25570-VOUT_SET)") (class "Default")
      (node (ref "BQ25570") (pin "12") (pinfunction "VOUT_SET_12") (pintype "passive"))
      (node (ref "Rout1") (pin "2") (pinfunction "2_2") (pintype "passive"))
      (node (ref "Rout2") (pin "1") (pinfunction "1_1") (pintype "passive"))
    )
    (net (code "52") (name "Net-(BQ25570-VRDIV)") (class "Default")
      (node (ref "BQ25570") (pin "8") (pinfunction "VRDIV_8") (pintype "passive"))
      (node (ref "Rok3") (pin "1") (pinfunction "1_1") (pintype "passive"))
      (node (ref "Rout2") (pin "2") (pinfunction "2_2") (pintype "passive"))
      (node (ref "Rov2") (pin "2") (pinfunction "2_2") (pintype "passive"))
    )
    (net (code "53") (name "Net-(BQ25570-VREF_SAMP)") (class "Default")
      (node (ref "BQ25570") (pin "4") (pinfunction "VREF_SAMP_4") (pintype "passive"))
      (node (ref "C14") (pin "1") (pinfunction "1_1") (pintype "passive"))
    )
    (net (code "54") (name "Net-(BQ25570-VSTOR)") (class "Default")
      (node (ref "BQ25570") (pin "19") (pinfunction "VSTOR_19") (pintype "passive"))
      (node (ref "C15") (pin "1") (pinfunction "1_1") (pintype "passive"))
      (node (ref "C16") (pin "2") (pinfunction "2_2") (pintype "passive"))
    )
    (net (code "55") (name "Net-(C6-Pad1)") (class "Default")
      (node (ref "C6") (pin "1") (pinfunction "1_1") (pintype "passive"))
      (node (ref "L2") (pin "2") (pinfunction "2_2") (pintype "passive"))
    )
    (net (code "56") (name "Net-(C6A-Pad1)") (class "Default")
      (node (ref "C6A") (pin "1") (pinfunction "1_1") (pintype "passive"))
      (node (ref "R6A") (pin "2") (pinfunction "2_2") (pintype "passive"))
    )
    (net (code "57") (name "Net-(C7-Pad2)") (class "Default")
      (node (ref "C7") (pin "2") (pinfunction "2_2") (pintype "passive"))
      (node (ref "L3") (pin "2") (pinfunction "2_2") (pintype "passive"))
      (node (ref "L4") (pin "1") (pinfunction "1_1") (pintype "passive"))
    )
    (net (code "58") (name "Net-(C8-Pad2)") (class "Default")
      (node (ref "C8") (pin "2") (pinfunction "2_2") (pintype "passive"))
      (node (ref "L4") (pin "2") (pinfunction "2_2") (pintype "passive"))
      (node (ref "L5") (pin "1") (pinfunction "1_1") (pintype "passive"))
    )
    (net (code "59") (name "Net-(C9-Pad1)") (class "Default")
      (node (ref "C9") (pin "1") (pinfunction "1_1") (pintype "passive"))
      (node (ref "L5") (pin "2") (pinfunction "2_2") (pintype "passive"))
    )
    (net (code "60") (name "Net-(C10-Pad1)") (class "Default")
      (node (ref "C10") (pin "1") (pinfunction "1_1") (pintype "passive"))
      (node (ref "C9") (pin "2") (pinfunction "2_2") (pintype "passive"))
    )
    (net (code "61") (name "Net-(D1A-K)") (class "Default")
      (node (ref "C5A") (pin "2") (pinfunction "2_2") (pintype "passive"))
      (node (ref "D1A") (pin "1") (pinfunction "K_1") (pintype "passive"))
      (node (ref "R1A") (pin "1") (pinfunction "1_1") (pintype "passive"))
      (node (ref "U2") (pin "2") (pinfunction "IN_2") (pintype "passive"))
    )
    (net (code "62") (name "Net-(D2A-K)") (class "Default")
      (node (ref "C2A") (pin "1") (pinfunction "1_1") (pintype "passive"))
      (node (ref "D2A") (pin "1") (pinfunction "K_1") (pintype "passive"))
      (node (ref "L1A") (pin "1") (pinfunction "1_1") (pintype "passive"))
      (node (ref "U2") (pin "3") (pinfunction "OUT_3") (pintype "passive"))
    )
    (net (code "63") (name "Net-(E1-A)") (class "Default")
      (node (ref "E1") (pin "1") (pinfunction "A_1") (pintype "passive"))
      (node (ref "SW1") (pin "5") (pinfunction "IN_5") (pintype "passive"))
    )
    (net (code "64") (name "Net-(E2-A)") (class "Default")
      (node (ref "E2") (pin "1") (pinfunction "A_1") (pintype "passive"))
      (node (ref "SW1") (pin "1") (pinfunction "OUT1_1") (pintype "passive"))
      (node (ref "SW2") (pin "5") (pinfunction "IN_5") (pintype "passive"))
    )
    (net (code "65") (name "Net-(E3-A)") (class "Default")
      (node (ref "E3") (pin "1") (pinfunction "A_1") (pintype "passive"))
      (node (ref "SW2") (pin "1") (pinfunction "OUT1_1") (pintype "passive"))
      (node (ref "SW3") (pin "5") (pinfunction "IN_5") (pintype "passive"))
    )
    (net (code "66") (name "Net-(E4-A)") (class "Default")
      (node (ref "E4") (pin "1") (pinfunction "A_1") (pintype "passive"))
      (node (ref "SW3") (pin "1") (pinfunction "OUT1_1") (pintype "passive"))
      (node (ref "SW4") (pin "5") (pinfunction "IN_5") (pintype "passive"))
    )
    (net (code "67") (name "Net-(E5-A)") (class "Default")
      (node (ref "E5") (pin "1") (pinfunction "A_1") (pintype "passive"))
      (node (ref "SW4") (pin "1") (pinfunction "OUT1_1") (pintype "passive"))
      (node (ref "SW5") (pin "5") (pinfunction "IN_5") (pintype "passive"))
    )
    (net (code "68") (name "Net-(E6-A)") (class "Default")
      (node (ref "E6") (pin "1") (pinfunction "A_1") (pintype "passive"))
      (node (ref "SW5") (pin "1") (pinfunction "OUT1_1") (pintype "passive"))
    )
    (net (code "69") (name "Net-(E7-A)") (class "Default")
      (node (ref "E7") (pin "1") (pinfunction "A_1") (pintype "passive"))
      (node (ref "SW6") (pin "5") (pinfunction "IN_5") (pintype "passive"))
    )
    (net (code "70") (name "Net-(E8-A)") (class "Default")
      (node (ref "E8") (pin "1") (pinfunction "A_1") (pintype "passive"))
      (node (ref "SW6") (pin "1") (pinfunction "OUT1_1") (pintype "passive"))
      (node (ref "SW7") (pin "5") (pinfunction "IN_5") (pintype "passive"))
    )
    (net (code "71") (name "Net-(E9-A)") (class "Default")
      (node (ref "E9") (pin "1") (pinfunction "A_1") (pintype "passive"))
      (node (ref "SW7") (pin "1") (pinfunction "OUT1_1") (pintype "passive"))
      (node (ref "SW8") (pin "5") (pinfunction "IN_5") (pintype "passive"))
    )
    (net (code "72") (name "Net-(E10-A)") (class "Default")
      (node (ref "E10") (pin "1") (pinfunction "A_1") (pintype "passive"))
      (node (ref "SW8") (pin "1") (pinfunction "OUT1_1") (pintype "passive"))
      (node (ref "SW9") (pin "5") (pinfunction "IN_5") (pintype "passive"))
    )
    (net (code "73") (name "Net-(E11-A)") (class "Default")
      (node (ref "E11") (pin "1") (pinfunction "A_1") (pintype "passive"))
      (node (ref "SW10") (pin "5") (pinfunction "IN_5") (pintype "passive"))
      (node (ref "SW9") (pin "1") (pinfunction "OUT1_1") (pintype "passive"))
    )
    (net (code "74") (name "Net-(E12-A)") (class "Default")
      (node (ref "E12") (pin "1") (pinfunction "A_1") (pintype "passive"))
      (node (ref "SW10") (pin "1") (pinfunction "OUT1_1") (pintype "passive"))
    )
    (net (code "75") (name "Net-(E13-A)") (class "Default")
      (node (ref "E13") (pin "1") (pinfunction "A_1") (pintype "passive"))
      (node (ref "SW11") (pin "5") (pinfunction "IN_5") (pintype "passive"))
    )
    (net (code "76") (name "Net-(E14-A)") (class "Default")
      (node (ref "E14") (pin "1") (pinfunction "A_1") (pintype "passive"))
      (node (ref "SW11") (pin "1") (pinfunction "OUT1_1") (pintype "passive"))
      (node (ref "SW12") (pin "5") (pinfunction "IN_5") (pintype "passive"))
    )
    (net (code "77") (name "Net-(E15-A)") (class "Default")
      (node (ref "E15") (pin "1") (pinfunction "A_1") (pintype "passive"))
      (node (ref "SW12") (pin "1") (pinfunction "OUT1_1") (pintype "passive"))
      (node (ref "SW13") (pin "5") (pinfunction "IN_5") (pintype "passive"))
    )
    (net (code "78") (name "Net-(E16-A)") (class "Default")
      (node (ref "E16") (pin "1") (pinfunction "A_1") (pintype "passive"))
      (node (ref "SW13") (pin "1") (pinfunction "OUT1_1") (pintype "passive"))
      (node (ref "SW14") (pin "5") (pinfunction "IN_5") (pintype "passive"))
    )
    (net (code "79") (name "Net-(E17-A)") (class "Default")
      (node (ref "E17") (pin "1") (pinfunction "A_1") (pintype "passive"))
      (node (ref "SW14") (pin "1") (pinfunction "OUT1_1") (pintype "passive"))
      (node (ref "SW15") (pin "5") (pinfunction "IN_5") (pintype "passive"))
    )
    (net (code "80") (name "Net-(E18-A)") (class "Default")
      (node (ref "E18") (pin "1") (pinfunction "A_1") (pintype "passive"))
      (node (ref "SW15") (pin "1") (pinfunction "OUT1_1") (pintype "passive"))
    )
    (net (code "81") (name "Net-(E19-A)") (class "Default")
      (node (ref "E19") (pin "1") (pinfunction "A_1") (pintype "passive"))
      (node (ref "SW16") (pin "5") (pinfunction "IN_5") (pintype "passive"))
    )
    (net (code "82") (name "Net-(E20-A)") (class "Default")
      (node (ref "E20") (pin "1") (pinfunction "A_1") (pintype "passive"))
      (node (ref "SW16") (pin "1") (pinfunction "OUT1_1") (pintype "passive"))
      (node (ref "SW17") (pin "5") (pinfunction "IN_5") (pintype "passive"))
    )
    (net (code "83") (name "Net-(E21-A)") (class "Default")
      (node (ref "E21") (pin "1") (pinfunction "A_1") (pintype "passive"))
      (node (ref "SW17") (pin "1") (pinfunction "OUT1_1") (pintype "passive"))
      (node (ref "SW18") (pin "5") (pinfunction "IN_5") (pintype "passive"))
    )
    (net (code "84") (name "Net-(E22-A)") (class "Default")
      (node (ref "E22") (pin "1") (pinfunction "A_1") (pintype "passive"))
      (node (ref "SW18") (pin "1") (pinfunction "OUT1_1") (pintype "passive"))
      (node (ref "SW19") (pin "5") (pinfunction "IN_5") (pintype "passive"))
    )
    (net (code "85") (name "Net-(E23-A)") (class "Default")
      (node (ref "E23") (pin "1") (pinfunction "A_1") (pintype "passive"))
      (node (ref "SW19") (pin "1") (pinfunction "OUT1_1") (pintype "passive"))
      (node (ref "SW20") (pin "5") (pinfunction "IN_5") (pintype "passive"))
    )
    (net (code "86") (name "Net-(E24-A)") (class "Default")
      (node (ref "E24") (pin "1") (pinfunction "A_1") (pintype "passive"))
      (node (ref "SW20") (pin "1") (pinfunction "OUT1_1") (pintype "passive"))
    )
    (net (code "87") (name "Net-(E25-A)") (class "Default")
      (node (ref "E25") (pin "1") (pinfunction "A_1") (pintype "passive"))
      (node (ref "SW21") (pin "5") (pinfunction "IN_5") (pintype "passive"))
    )
    (net (code "88") (name "Net-(E26-A)") (class "Default")
      (node (ref "E26") (pin "1") (pinfunction "A_1") (pintype "passive"))
      (node (ref "SW21") (pin "1") (pinfunction "OUT1_1") (pintype "passive"))
      (node (ref "SW22") (pin "5") (pinfunction "IN_5") (pintype "passive"))
    )
    (net (code "89") (name "Net-(E27-A)") (class "Default")
      (node (ref "E27") (pin "1") (pinfunction "A_1") (pintype "passive"))
      (node (ref "SW22") (pin "1") (pinfunction "OUT1_1") (pintype "passive"))
      (node (ref "SW23") (pin "5") (pinfunction "IN_5") (pintype "passive"))
    )
    (net (code "90") (name "Net-(E28-A)") (class "Default")
      (node (ref "E28") (pin "1") (pinfunction "A_1") (pintype "passive"))
      (node (ref "SW23") (pin "1") (pinfunction "OUT1_1") (pintype "passive"))
      (node (ref "SW24") (pin "5") (pinfunction "IN_5") (pintype "passive"))
    )
    (net (code "91") (name "Net-(E29-A)") (class "Default")
      (node (ref "E29") (pin "1") (pinfunction "A_1") (pintype "passive"))
      (node (ref "SW24") (pin "1") (pinfunction "OUT1_1") (pintype "passive"))
      (node (ref "SW25") (pin "5") (pinfunction "IN_5") (pintype "passive"))
    )
    (net (code "92") (name "Net-(E30-A)") (class "Default")
      (node (ref "E30") (pin "1") (pinfunction "A_1") (pintype "passive"))
      (node (ref "SW25") (pin "1") (pinfunction "OUT1_1") (pintype "passive"))
    )
    (net (code "93") (name "Net-(RM2-Pad1)") (class "Default")
      (node (ref "RM2") (pin "1") (pinfunction "1_1") (pintype "passive"))
      (node (ref "RM3") (pin "2") (pinfunction "2_2") (pintype "passive"))
    )
    (net (code "94") (name "Net-(U1-DCOUPL)") (class "Default")
      (node (ref "C4") (pin "2") (pinfunction "2_2") (pintype "passive"))
      (node (ref "U1") (pin "23") (pinfunction "DCOUPL_23") (pintype "passive"))
    )
    (net (code "95") (name "Net-(U1-X32K_Q1)") (class "Default")
      (node (ref "C2") (pin "2") (pinfunction "2_2") (pintype "passive"))
      (node (ref "U1") (pin "3") (pinfunction "X32K_Q1_3") (pintype "passive"))
      (node (ref "Y1") (pin "2") (pinfunction "OSC2_2") (pintype "passive"))
    )
    (net (code "96") (name "Net-(U1-X32K_Q2)") (class "Default")
      (node (ref "C3") (pin "2") (pinfunction "2_2") (pintype "passive"))
      (node (ref "U1") (pin "4") (pinfunction "X32K_Q2_4") (pintype "passive"))
      (node (ref "Y1") (pin "1") (pinfunction "OSC1_1") (pintype "passive"))
    )
    (net (code "97") (name "Net-(U1-X48M_N)") (class "Default")
      (node (ref "U1") (pin "46") (pinfunction "X48M_N_46") (pintype "passive"))
      (node (ref "Y2") (pin "2") (pinfunction "OSC2_2") (pintype "passive"))
    )
    (net (code "98") (name "Net-(U1-X48M_P)") (class "Default")
      (node (ref "U1") (pin "47") (pinfunction "X48M_P_47") (pintype "passive"))
      (node (ref "Y2") (pin "1") (pinfunction "OSC1_1") (pintype "passive"))
    )
    (net (code "99") (name "Net-(U2-BS)") (class "Default")
      (node (ref "C2A") (pin "2") (pinfunction "2_2") (pintype "passive"))
      (node (ref "U2") (pin "1") (pinfunction "BS_1") (pintype "passive"))
    )
    (net (code "100") (name "Net-(U2-CP)") (class "Default")
      (node (ref "C6A") (pin "2") (pinfunction "2_2") (pintype "passive"))
      (node (ref "U2") (pin "6") (pinfunction "CP_6") (pintype "passive"))
    )
    (net (code "101") (name "Net-(U2-O{slash}F)") (class "Default")
      (node (ref "R1A") (pin "2") (pinfunction "2_2") (pintype "passive"))
      (node (ref "U2") (pin "7") (pinfunction "O/F_7") (pintype "passive"))
    )
    (net (code "102") (name "Net-(U2-SS)") (class "Default")
      (node (ref "C1A") (pin "2") (pinfunction "2_2") (pintype "passive"))
      (node (ref "U2") (pin "8") (pinfunction "SS_8") (pintype "passive"))
    )
    (net (code "103") (name "Net-(U2-VA)") (class "Default")
      (node (ref "R3A") (pin "1") (pinfunction "1_1") (pintype "passive"))
      (node (ref "R5A") (pin "2") (pinfunction "2_2") (pintype "passive"))
      (node (ref "U2") (pin "5") (pinfunction "VA_5") (pintype "passive"))
    )
    (net (code "104") (name "VDDR") (class "Default")
      (node (ref "C105") (pin "2") (pinfunction "2_2") (pintype "passive"))
      (node (ref "C106") (pin "2") (pinfunction "2_2") (pintype "passive"))
      (node (ref "C107") (pin "2") (pinfunction "2_2") (pintype "passive"))
      (node (ref "L1") (pin "2") (pinfunction "2_2") (pintype "passive"))
      (node (ref "U1") (pin "45") (pinfunction "VDDR_45") (pintype "passive"))
      (node (ref "U1") (pin "48") (pinfunction "VDDR_48") (pintype "passive"))
    )
    (net (code "105") (name "VDDS") (class "Default")
      (node (ref "C101") (pin "2") (pinfunction "2_2") (pintype "passive"))
      (node (ref "C102") (pin "2") (pinfunction "2_2") (pintype "passive"))
      (node (ref "C103") (pin "2") (pinfunction "2_2") (pintype "passive"))
      (node (ref "C104") (pin "2") (pinfunction "2_2") (pintype "passive"))
      (node (ref "C99") (pin "2") (pinfunction "2_2") (pintype "passive"))
      (node (ref "P2") (pin "3") (pinfunction "3_3") (pintype "passive"))
      (node (ref "P4") (pin "2") (pinfunction "2_2") (pintype "passive"))
      (node (ref "R1") (pin "2") (pinfunction "2_2") (pintype "passive"))
      (node (ref "U1") (pin "13") (pinfunction "VDDS2_13") (pintype "passive"))
      (node (ref "U1") (pin "22") (pinfunction "VDDS3_22") (pintype "passive"))
      (node (ref "U1") (pin "34") (pinfunction "VDDS_DCDC_34") (pintype "passive"))
      (node (ref "U1") (pin "44") (pinfunction "VDDS_44") (pintype "passive"))
    )
    (net (code "106") (name "unconnected-(SW1-OUT2-Pad3)") (class "Default")
      (node (ref "SW1") (pin "3") (pinfunction "OUT2_3") (pintype "passive"))
    )
    (net (code "107") (name "unconnected-(SW2-OUT2-Pad3)") (class "Default")
      (node (ref "SW2") (pin "3") (pinfunction "OUT2_3") (pintype "passive"))
    )
    (net (code "108") (name "unconnected-(SW3-OUT2-Pad3)") (class "Default")
      (node (ref "SW3") (pin "3") (pinfunction "OUT2_3") (pintype "passive"))
    )
    (net (code "109") (name "unconnected-(SW4-OUT2-Pad3)") (class "Default")
      (node (ref "SW4") (pin "3") (pinfunction "OUT2_3") (pintype "passive"))
    )
    (net (code "110") (name "unconnected-(SW5-OUT2-Pad3)") (class "Default")
      (node (ref "SW5") (pin "3") (pinfunction "OUT2_3") (pintype "passive"))
    )
    (net (code "111") (name "unconnected-(SW6-OUT2-Pad3)") (class "Default")
      (node (ref "SW6") (pin "3") (pinfunction "OUT2_3") (pintype "passive"))
    )
    (net (code "112") (name "unconnected-(SW7-OUT2-Pad3)") (class "Default")
      (node (ref "SW7") (pin "3") (pinfunction "OUT2_3") (pintype "passive"))
    )
    (net (code "113") (name "unconnected-(SW8-OUT2-Pad3)") (class "Default")
      (node (ref "SW8") (pin "3") (pinfunction "OUT2_3") (pintype "passive"))
    )
    (net (code "114") (name "unconnected-(SW9-OUT2-Pad3)") (class "Default")
      (node (ref "SW9") (pin "3") (pinfunction "OUT2_3") (pintype "passive"))
    )
    (net (code "115") (name "unconnected-(SW10-OUT2-Pad3)") (class "Default")
      (node (ref "SW10") (pin "3") (pinfunction "OUT2_3") (pintype "passive"))
    )
    (net (code "116") (name "unconnected-(SW11-OUT2-Pad3)") (class "Default")
      (node (ref "SW11") (pin "3") (pinfunction "OUT2_3") (pintype "passive"))
    )
    (net (code "117") (name "unconnected-(SW12-OUT2-Pad3)") (class "Default")
      (node (ref "SW12") (pin "3") (pinfunction "OUT2_3") (pintype "passive"))
    )
    (net (code "118") (name "unconnected-(SW13-OUT2-Pad3)") (class "Default")
      (node (ref "SW13") (pin "3") (pinfunction "OUT2_3") (pintype "passive"))
    )
    (net (code "119") (name "unconnected-(SW14-OUT2-Pad3)") (class "Default")
      (node (ref "SW14") (pin "3") (pinfunction "OUT2_3") (pintype "passive"))
    )
    (net (code "120") (name "unconnected-(SW15-OUT2-Pad3)") (class "Default")
      (node (ref "SW15") (pin "3") (pinfunction "OUT2_3") (pintype "passive"))
    )
    (net (code "121") (name "unconnected-(SW16-OUT2-Pad3)") (class "Default")
      (node (ref "SW16") (pin "3") (pinfunction "OUT2_3") (pintype "passive"))
    )
    (net (code "122") (name "unconnected-(SW17-OUT2-Pad3)") (class "Default")
      (node (ref "SW17") (pin "3") (pinfunction "OUT2_3") (pintype "passive"))
    )
    (net (code "123") (name "unconnected-(SW18-OUT2-Pad3)") (class "Default")
      (node (ref "SW18") (pin "3") (pinfunction "OUT2_3") (pintype "passive"))
    )
    (net (code "124") (name "unconnected-(SW19-OUT2-Pad3)") (class "Default")
      (node (ref "SW19") (pin "3") (pinfunction "OUT2_3") (pintype "passive"))
    )
    (net (code "125") (name "unconnected-(SW20-OUT2-Pad3)") (class "Default")
      (node (ref "SW20") (pin "3") (pinfunction "OUT2_3") (pintype "passive"))
    )
    (net (code "126") (name "unconnected-(SW21-OUT2-Pad3)") (class "Default")
      (node (ref "SW21") (pin "3") (pinfunction "OUT2_3") (pintype "passive"))
    )
    (net (code "127") (name "unconnected-(SW22-OUT2-Pad3)") (class "Default")
      (node (ref "SW22") (pin "3") (pinfunction "OUT2_3") (pintype "passive"))
    )
    (net (code "128") (name "unconnected-(SW23-OUT2-Pad3)") (class "Default")
      (node (ref "SW23") (pin "3") (pinfunction "OUT2_3") (pintype "passive"))
    )
    (net (code "129") (name "unconnected-(SW24-OUT2-Pad3)") (class "Default")
      (node (ref "SW24") (pin "3") (pinfunction "OUT2_3") (pintype "passive"))
    )
    (net (code "130") (name "unconnected-(SW25-OUT2-Pad3)") (class "Default")
      (node (ref "SW25") (pin "3") (pinfunction "OUT2_3") (pintype "passive"))
    )
  )
)
